# MainBoard_Power.net
KiCad netlist of a schematic drawn in Altium Designer
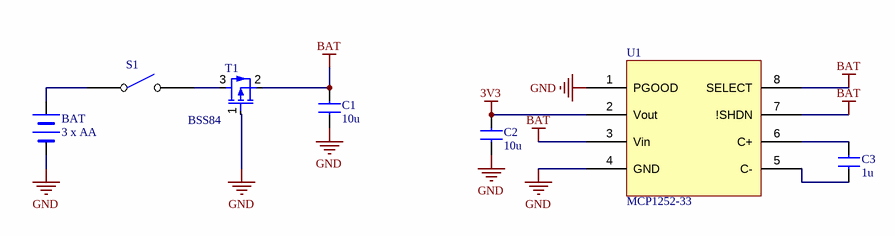
[diagram p0: MainBoard_Power.SchDoc]

(export (version "E")
  (design (tool "Eeschema 10.0.6"))
  (components
    (comp (ref "BAT") (value "3 x AA") (footprint "SIP2") (libsource (lib "DEVICE_HSLU") (part "BATTERY")))
    (comp (ref "C1")
      (value "10u")
      (footprint "0805_C")
      (description "Normaler Kondensator")
      (libsource (lib "MainBoard") (part "C?"))
    )
    (comp (ref "C2")
      (value "10u")
      (footprint "0805_C")
      (description "Normaler Kondensator")
      (libsource (lib "MainBoard") (part "C?"))
    )
    (comp (ref "C3")
      (value "1u")
      (footprint "0805_C")
      (description "Normaler Kondensator")
      (libsource (lib "MainBoard") (part "C?"))
    )
    (comp (ref "S1") (value "SW SPST") (footprint "SIP2") (libsource (lib "DEVICE_HSLU") (part "SW SPST")))
    (comp (ref "T1")
      (value "BSS84")
      (footprint "SOT23-3")
      (description "MOSFET-P 1G,2D,3S (Diode)")
      (libsource (lib "Sch_Lib") (part "MOSFET-P 1G,2D,3S (Diode)"))
    )
    (comp (ref "U1") (value "MCP1252-33") (footprint "MSOP8") (libsource (lib "MainBoard") (part "VOLTREG")))
  )
  (nets
    (net (code "1") (name "3V3") (class "Default")
      (node (ref "C2") (pin "2") (pinfunction "2_2") (pintype "passive"))
      (node (ref "U1") (pin "2") (pinfunction "Vout_2") (pintype "passive"))
    )
    (net (code "2") (name "BAT") (class "Default")
      (node (ref "C1") (pin "2") (pinfunction "2_2") (pintype "passive"))
      (node (ref "T1") (pin "2") (pinfunction "S_2") (pintype "passive"))
      (node (ref "U1") (pin "3") (pinfunction "Vin_3") (pintype "passive"))
      (node (ref "U1") (pin "7") (pinfunction "!SHDN_7") (pintype "passive"))
      (node (ref "U1") (pin "8") (pinfunction "SELECT_8") (pintype "passive"))
    )
    (net (code "3") (name "GND") (class "Default")
      (node (ref "BAT") (pin "2") (pintype "passive"))
      (node (ref "C1") (pin "1") (pinfunction "1_1") (pintype "passive"))
      (node (ref "C2") (pin "1") (pinfunction "1_1") (pintype "passive"))
      (node (ref "T1") (pin "1") (pinfunction "G_1") (pintype "passive"))
      (node (ref "U1") (pin "1") (pinfunction "PGOOD_1") (pintype "passive"))
      (node (ref "U1") (pin "4") (pinfunction "GND_4") (pintype "passive"))
    )
    (net (code "4") (name "Net-(S1-COMMON)") (class "Default")
      (node (ref "BAT") (pin "1") (pintype "passive"))
      (node (ref "S1") (pin "1") (pinfunction "COMMON_1") (pintype "passive"))
    )
    (net (code "5") (name "Net-(S1-NO)") (class "Default")
      (node (ref "S1") (pin "2") (pinfunction "NO_2") (pintype "passive"))
      (node (ref "T1") (pin "3") (pinfunction "D_3") (pintype "passive"))
    )
    (net (code "6") (name "Net-(U1-C+)") (class "Default")
      (node (ref "C3") (pin "2") (pinfunction "2_2") (pintype "passive"))
      (node (ref "U1") (pin "6") (pinfunction "C+_6") (pintype "passive"))
    )
    (net (code "7") (name "Net-(U1-C-)") (class "Default")
      (node (ref "C3") (pin "1") (pinfunction "1_1") (pintype "passive"))
      (node (ref "U1") (pin "5") (pinfunction "C-_5") (pintype "passive"))
    )
  )
)
